# d701-vs1053-synth.net
KiCad netlist of a schematic drawn in EAGLE
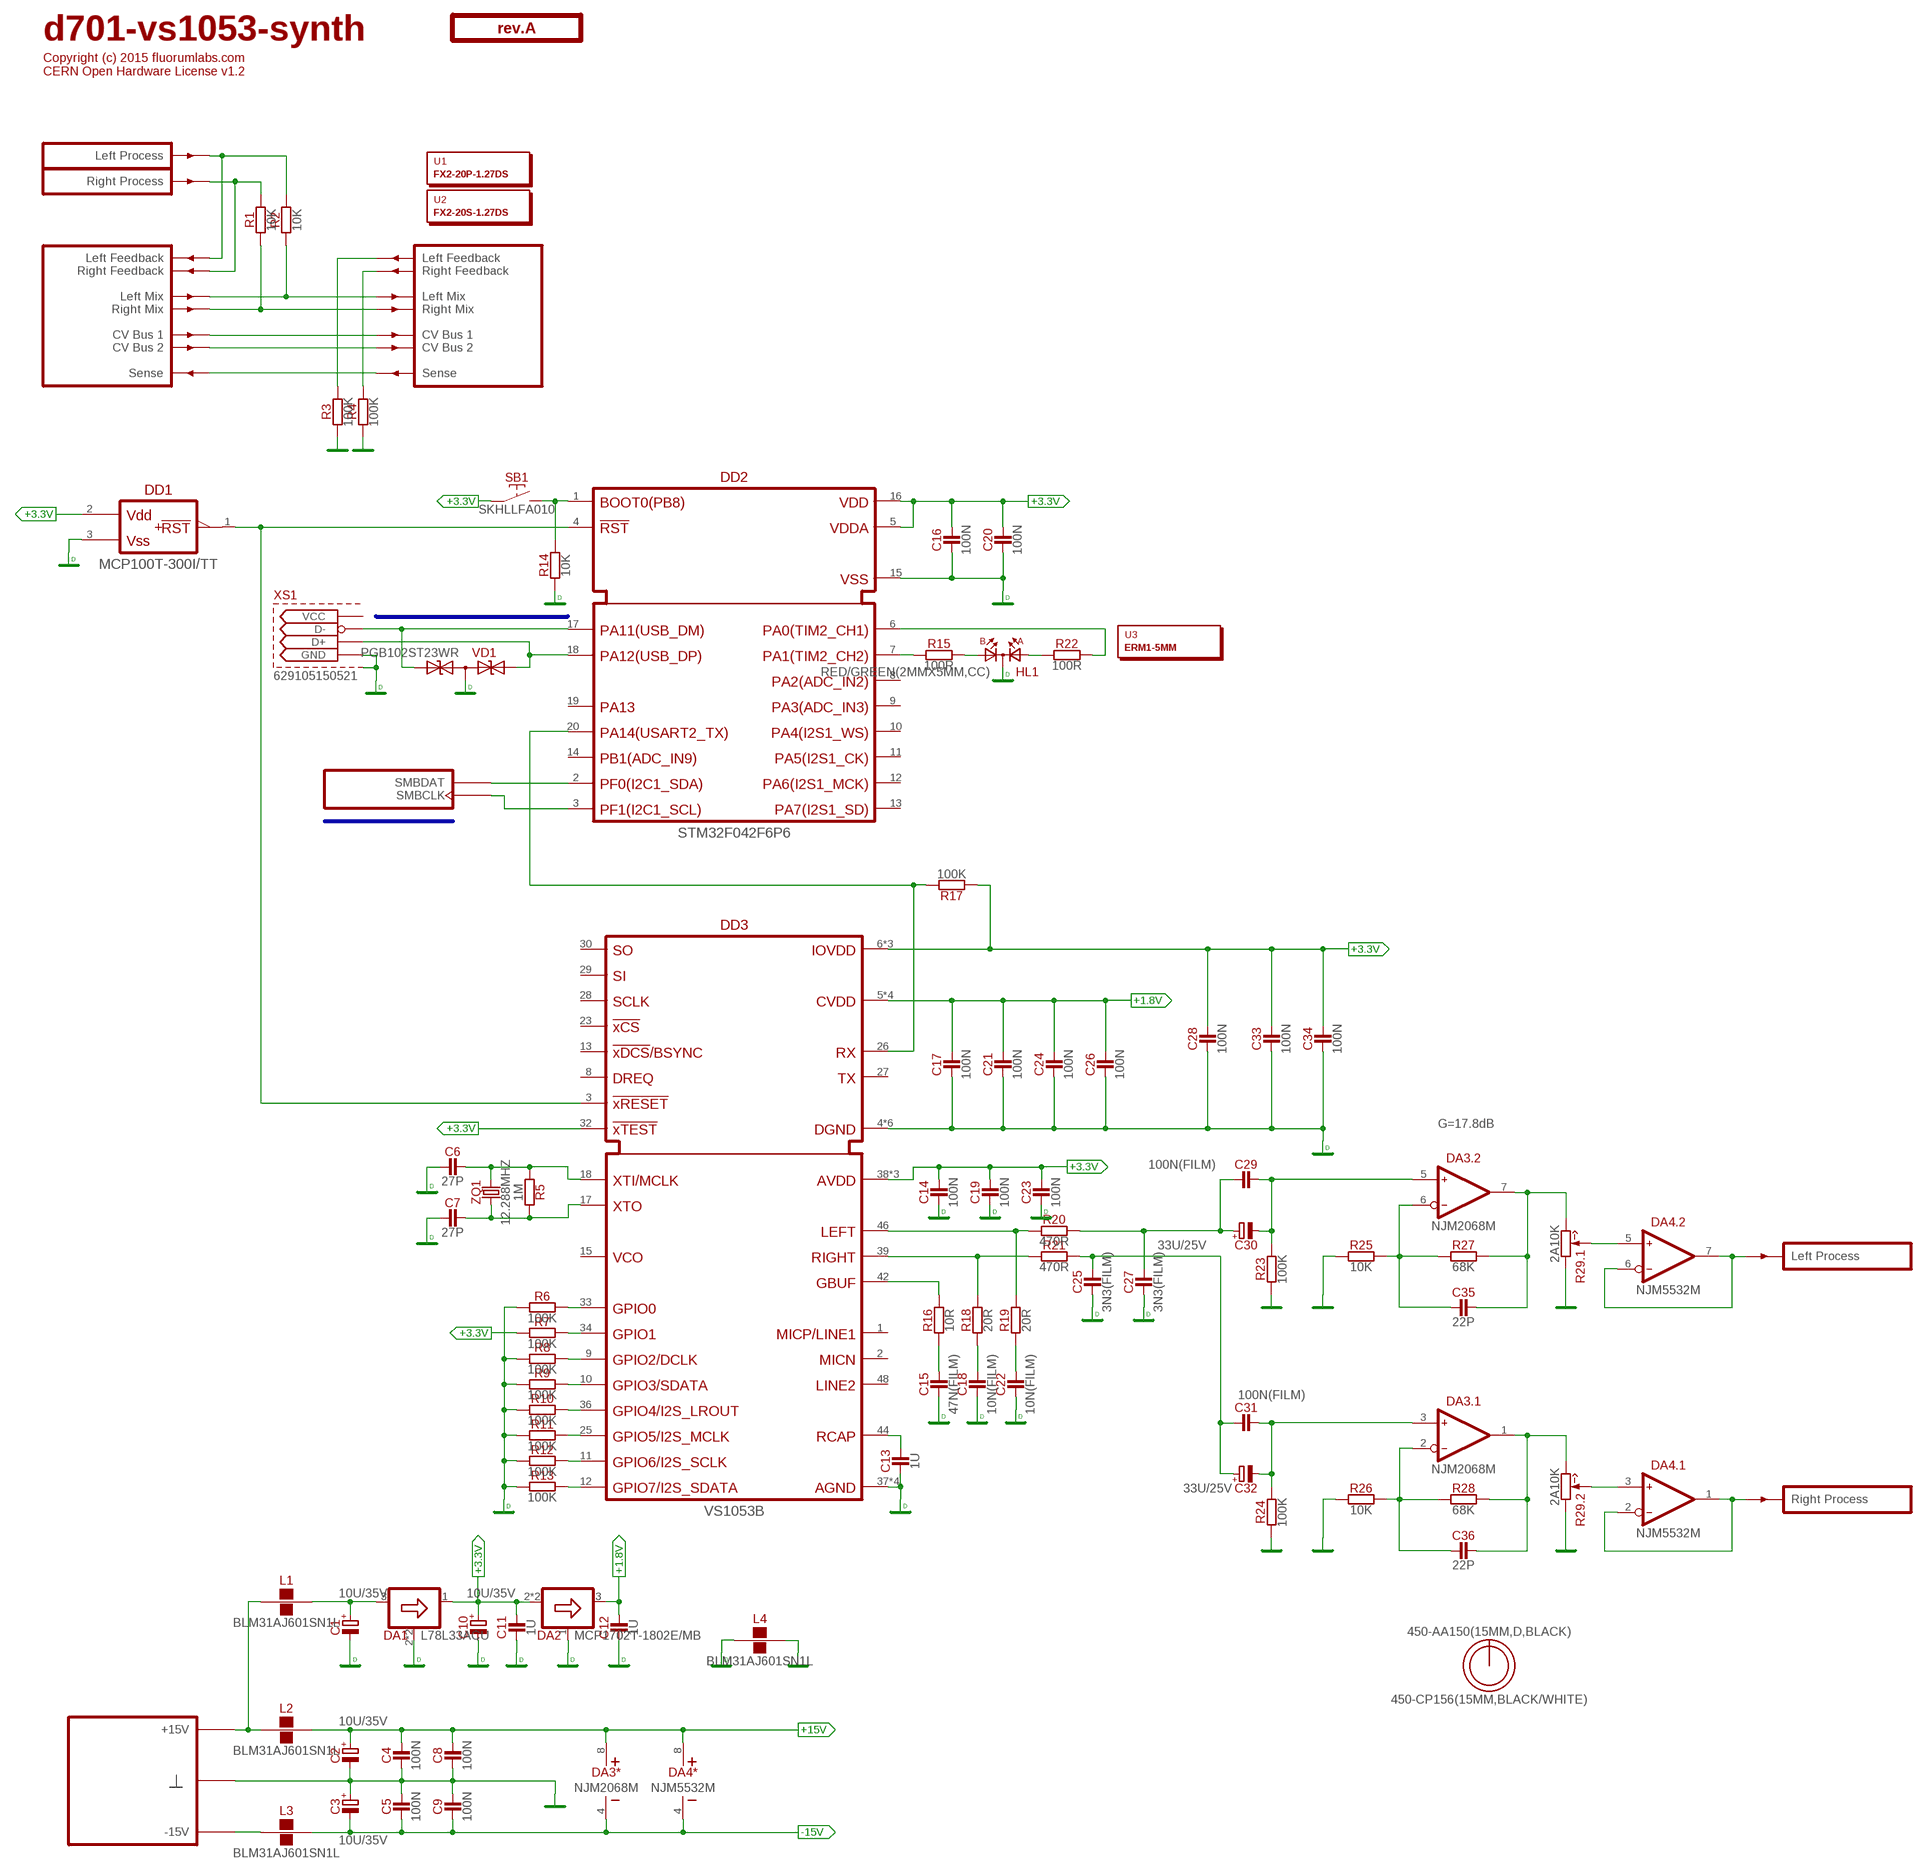
[diagram p0: schematic, sheet 1]

(export (version "E")
  (design (tool "Eeschema 10.0.6"))
  (components
    (comp (ref "C1")
      (value "10U/35V")
      (footprint "eagle-import:E2-5")
      (libsource (lib "eagle-import") (part "?10U/35V"))
    )
    (comp (ref "C2")
      (value "10U/35V")
      (footprint "eagle-import:E2-5")
      (libsource (lib "eagle-import") (part "?10U/35V"))
    )
    (comp (ref "C3")
      (value "10U/35V")
      (footprint "eagle-import:E2-5")
      (libsource (lib "eagle-import") (part "?10U/35V"))
    )
    (comp (ref "C4")
      (value "100N")
      (footprint "eagle-import:C-0805")
      (libsource (lib "eagle-import") (part "?100N"))
    )
    (comp (ref "C5")
      (value "100N")
      (footprint "eagle-import:C-0805")
      (libsource (lib "eagle-import") (part "?100N"))
    )
    (comp (ref "C6")
      (value "27P")
      (footprint "eagle-import:C-0805")
      (libsource (lib "eagle-import") (part "?27P"))
    )
    (comp (ref "C7")
      (value "27P")
      (footprint "eagle-import:C-0805")
      (libsource (lib "eagle-import") (part "?27P"))
    )
    (comp (ref "C8")
      (value "100N")
      (footprint "eagle-import:C-0805")
      (libsource (lib "eagle-import") (part "?100N"))
    )
    (comp (ref "C9")
      (value "100N")
      (footprint "eagle-import:C-0805")
      (libsource (lib "eagle-import") (part "?100N"))
    )
    (comp (ref "C10")
      (value "10U/35V")
      (footprint "eagle-import:E2-5")
      (libsource (lib "eagle-import") (part "?10U/35V"))
    )
    (comp (ref "C11")
      (value "1U")
      (footprint "eagle-import:C-0805")
      (libsource (lib "eagle-import") (part "?1U"))
    )
    (comp (ref "C12")
      (value "1U")
      (footprint "eagle-import:C-0805")
      (libsource (lib "eagle-import") (part "?1U"))
    )
    (comp (ref "C13")
      (value "1U")
      (footprint "eagle-import:C-0805")
      (libsource (lib "eagle-import") (part "?1U"))
    )
    (comp (ref "C14")
      (value "100N")
      (footprint "eagle-import:C-0805")
      (libsource (lib "eagle-import") (part "?100N"))
    )
    (comp (ref "C15")
      (value "47N(FILM)")
      (footprint "eagle-import:C050-025X075")
      (libsource (lib "eagle-import") (part "?47N(FILM)"))
    )
    (comp (ref "C16")
      (value "100N")
      (footprint "eagle-import:C-0805")
      (libsource (lib "eagle-import") (part "?100N"))
    )
    (comp (ref "C17")
      (value "100N")
      (footprint "eagle-import:C-0805")
      (libsource (lib "eagle-import") (part "?100N"))
    )
    (comp (ref "C18")
      (value "10N(FILM)")
      (footprint "eagle-import:C050-025X075")
      (libsource (lib "eagle-import") (part "?10N(FILM)"))
    )
    (comp (ref "C19")
      (value "100N")
      (footprint "eagle-import:C-0805")
      (libsource (lib "eagle-import") (part "?100N"))
    )
    (comp (ref "C20")
      (value "100N")
      (footprint "eagle-import:C-0805")
      (libsource (lib "eagle-import") (part "?100N"))
    )
    (comp (ref "C21")
      (value "100N")
      (footprint "eagle-import:C-0805")
      (libsource (lib "eagle-import") (part "?100N"))
    )
    (comp (ref "C22")
      (value "10N(FILM)")
      (footprint "eagle-import:C050-025X075")
      (libsource (lib "eagle-import") (part "?10N(FILM)"))
    )
    (comp (ref "C23")
      (value "100N")
      (footprint "eagle-import:C-0805")
      (libsource (lib "eagle-import") (part "?100N"))
    )
    (comp (ref "C24")
      (value "100N")
      (footprint "eagle-import:C-0805")
      (libsource (lib "eagle-import") (part "?100N"))
    )
    (comp (ref "C25")
      (value "3N3(FILM)")
      (footprint "eagle-import:C050-025X075")
      (libsource (lib "eagle-import") (part "?3N3(FILM)"))
    )
    (comp (ref "C26")
      (value "100N")
      (footprint "eagle-import:C-0805")
      (libsource (lib "eagle-import") (part "?100N"))
    )
    (comp (ref "C27")
      (value "3N3(FILM)")
      (footprint "eagle-import:C050-025X075")
      (libsource (lib "eagle-import") (part "?3N3(FILM)"))
    )
    (comp (ref "C28")
      (value "100N")
      (footprint "eagle-import:C-0805")
      (libsource (lib "eagle-import") (part "?100N"))
    )
    (comp (ref "C29")
      (value "100N(FILM)")
      (footprint "eagle-import:C050-025X075")
      (libsource (lib "eagle-import") (part "?100N(FILM)"))
    )
    (comp (ref "C30")
      (value "33U/25V")
      (footprint "eagle-import:E2,5-7")
      (libsource (lib "eagle-import") (part "?33U/25V"))
    )
    (comp (ref "C31")
      (value "100N(FILM)")
      (footprint "eagle-import:C050-025X075")
      (libsource (lib "eagle-import") (part "?100N(FILM)"))
    )
    (comp (ref "C32")
      (value "33U/25V")
      (footprint "eagle-import:E2,5-7")
      (libsource (lib "eagle-import") (part "?33U/25V"))
    )
    (comp (ref "C33")
      (value "100N")
      (footprint "eagle-import:C-0805")
      (libsource (lib "eagle-import") (part "?100N"))
    )
    (comp (ref "C34")
      (value "100N")
      (footprint "eagle-import:C-0805")
      (libsource (lib "eagle-import") (part "?100N"))
    )
    (comp (ref "C35")
      (value "22P")
      (footprint "eagle-import:C-0805")
      (libsource (lib "eagle-import") (part "?22P"))
    )
    (comp (ref "C36")
      (value "22P")
      (footprint "eagle-import:C-0805")
      (libsource (lib "eagle-import") (part "?22P"))
    )
    (comp (ref "DA1")
      (value "L78L33ACU")
      (footprint "eagle-import:SOT89")
      (libsource (lib "eagle-import") (part "?L78L33ACU"))
    )
    (comp (ref "DA2")
      (value "MCP1702T-1802E/MB")
      (footprint "eagle-import:SOT89")
      (libsource (lib "eagle-import") (part "?MCP1702T-1802E/MB"))
    )
    (comp (ref "DA3")
      (value "NJM2068M")
      (footprint "eagle-import:SO-8")
      (libsource (lib "eagle-import") (part "NJM2068M"))
    )
    (comp (ref "DA4")
      (value "NJM5532M")
      (footprint "eagle-import:SO-8")
      (libsource (lib "eagle-import") (part "NJM5532M"))
    )
    (comp (ref "DD1")
      (value "MCP100T-300I/TT")
      (footprint "eagle-import:SOT23")
      (libsource (lib "eagle-import") (part "MCP100T-300I/TT"))
    )
    (comp (ref "DD2")
      (value "STM32F042F6P6")
      (footprint "eagle-import:TSSOP20")
      (libsource (lib "eagle-import") (part "STM32F042F6P6"))
    )
    (comp (ref "DD3")
      (value "VS1053B")
      (footprint "eagle-import:LQFP48-7X7")
      (libsource (lib "eagle-import") (part "VS1053B"))
    )
    (comp (ref "HL1")
      (value "RED/GREEN(2MMX5MM,CC)")
      (footprint "eagle-import:LED2X5-3PIN")
      (libsource (lib "eagle-import") (part "?(2MMX5MM,CC)RED/GREEN"))
    )
    (comp (ref "L1")
      (value "BLM31AJ601SN1L")
      (footprint "eagle-import:1206")
      (libsource (lib "eagle-import") (part "BLM31AJ601SN1L"))
    )
    (comp (ref "L2")
      (value "BLM31AJ601SN1L")
      (footprint "eagle-import:1206")
      (libsource (lib "eagle-import") (part "BLM31AJ601SN1L"))
    )
    (comp (ref "L3")
      (value "BLM31AJ601SN1L")
      (footprint "eagle-import:1206")
      (libsource (lib "eagle-import") (part "BLM31AJ601SN1L"))
    )
    (comp (ref "L4")
      (value "BLM31AJ601SN1L")
      (footprint "eagle-import:1206")
      (libsource (lib "eagle-import") (part "BLM31AJ601SN1L"))
    )
    (comp (ref "O1")
      (value "TITLE")
      (footprint "eagle-import:EMPTY")
      (libsource (lib "eagle-import") (part "TITLE"))
    )
    (comp (ref "O2")
      (value "450-AA150(15MM,D,BLACK)")
      (footprint "eagle-import:EMPTY")
      (libsource (lib "eagle-import") (part "450-AA?150(15MM,D,BLACK)"))
    )
    (comp (ref "O3")
      (value "450-CP156(15MM,BLACK/WHITE)")
      (footprint "eagle-import:EMPTY")
      (libsource (lib "eagle-import") (part "450-C?P156(15MM,BLACK/WHITE)"))
    )
    (comp (ref "PCB1")
      (value "rev.A")
      (footprint "eagle-import:ST2-BOARD-50")
      (libsource (lib "eagle-import") (part "ST2-BOARD-?50"))
    )
    (comp (ref "R1")
      (value "10K")
      (footprint "eagle-import:R-0805")
      (libsource (lib "eagle-import") (part "?10K"))
    )
    (comp (ref "R2")
      (value "10K")
      (footprint "eagle-import:R-0805")
      (libsource (lib "eagle-import") (part "?10K"))
    )
    (comp (ref "R3")
      (value "100K")
      (footprint "eagle-import:R-0805")
      (libsource (lib "eagle-import") (part "?100K"))
    )
    (comp (ref "R4")
      (value "100K")
      (footprint "eagle-import:R-0805")
      (libsource (lib "eagle-import") (part "?100K"))
    )
    (comp (ref "R5")
      (value "1M")
      (footprint "eagle-import:R-0805")
      (libsource (lib "eagle-import") (part "?1M"))
    )
    (comp (ref "R6")
      (value "100K")
      (footprint "eagle-import:R-0805")
      (libsource (lib "eagle-import") (part "?100K"))
    )
    (comp (ref "R7")
      (value "100K")
      (footprint "eagle-import:R-0805")
      (libsource (lib "eagle-import") (part "?100K"))
    )
    (comp (ref "R8")
      (value "100K")
      (footprint "eagle-import:R-0805")
      (libsource (lib "eagle-import") (part "?100K"))
    )
    (comp (ref "R9")
      (value "100K")
      (footprint "eagle-import:R-0805")
      (libsource (lib "eagle-import") (part "?100K"))
    )
    (comp (ref "R10")
      (value "100K")
      (footprint "eagle-import:R-0805")
      (libsource (lib "eagle-import") (part "?100K"))
    )
    (comp (ref "R11")
      (value "100K")
      (footprint "eagle-import:R-0805")
      (libsource (lib "eagle-import") (part "?100K"))
    )
    (comp (ref "R12")
      (value "100K")
      (footprint "eagle-import:R-0805")
      (libsource (lib "eagle-import") (part "?100K"))
    )
    (comp (ref "R13")
      (value "100K")
      (footprint "eagle-import:R-0805")
      (libsource (lib "eagle-import") (part "?100K"))
    )
    (comp (ref "R14")
      (value "10K")
      (footprint "eagle-import:R-0805")
      (libsource (lib "eagle-import") (part "?10K"))
    )
    (comp (ref "R15")
      (value "100R")
      (footprint "eagle-import:R-0805")
      (libsource (lib "eagle-import") (part "?100R"))
    )
    (comp (ref "R16")
      (value "10R")
      (footprint "eagle-import:R-0805")
      (libsource (lib "eagle-import") (part "?10R"))
    )
    (comp (ref "R17")
      (value "100K")
      (footprint "eagle-import:R-0805")
      (libsource (lib "eagle-import") (part "?100K"))
    )
    (comp (ref "R18")
      (value "20R")
      (footprint "eagle-import:R-0805")
      (libsource (lib "eagle-import") (part "?20R"))
    )
    (comp (ref "R19")
      (value "20R")
      (footprint "eagle-import:R-0805")
      (libsource (lib "eagle-import") (part "?20R"))
    )
    (comp (ref "R20")
      (value "470R")
      (footprint "eagle-import:R-0805")
      (libsource (lib "eagle-import") (part "?470R"))
    )
    (comp (ref "R21")
      (value "470R")
      (footprint "eagle-import:R-0805")
      (libsource (lib "eagle-import") (part "?470R"))
    )
    (comp (ref "R22")
      (value "100R")
      (footprint "eagle-import:R-0805")
      (libsource (lib "eagle-import") (part "?100R"))
    )
    (comp (ref "R23")
      (value "100K")
      (footprint "eagle-import:R-0805")
      (libsource (lib "eagle-import") (part "?100K"))
    )
    (comp (ref "R24")
      (value "100K")
      (footprint "eagle-import:R-0805")
      (libsource (lib "eagle-import") (part "?100K"))
    )
    (comp (ref "R25")
      (value "10K")
      (footprint "eagle-import:R-0805")
      (libsource (lib "eagle-import") (part "?10K"))
    )
    (comp (ref "R26")
      (value "10K")
      (footprint "eagle-import:R-0805")
      (libsource (lib "eagle-import") (part "?10K"))
    )
    (comp (ref "R27")
      (value "68K")
      (footprint "eagle-import:R-0805")
      (libsource (lib "eagle-import") (part "?68K"))
    )
    (comp (ref "R28")
      (value "68K")
      (footprint "eagle-import:R-0805")
      (libsource (lib "eagle-import") (part "?68K"))
    )
    (comp (ref "R29")
      (value "2A10K")
      (footprint "eagle-import:RV11-DUAL")
      (libsource (lib "eagle-import") (part "2?A10K"))
    )
    (comp (ref "SB1")
      (value "SKHLLFA010")
      (footprint "eagle-import:SKHLLFA010")
      (libsource (lib "eagle-import") (part "SKHLLFA010"))
    )
    (comp (ref "U1")
      (value "FX2-20P-1.27DS")
      (footprint "eagle-import:EMPTY")
      (libsource (lib "eagle-import") (part "?FX2-20P-1.27DS"))
    )
    (comp (ref "U2")
      (value "FX2-20S-1.27DS")
      (footprint "eagle-import:EMPTY")
      (libsource (lib "eagle-import") (part "?FX2-20S-1.27DS"))
    )
    (comp (ref "U3")
      (value "ERM1-5MM")
      (footprint "eagle-import:EMPTY")
      (libsource (lib "eagle-import") (part "?ERM1-5MM"))
    )
    (comp (ref "VD1")
      (value "PGB102ST23WR")
      (footprint "eagle-import:SOT23")
      (libsource (lib "eagle-import") (part "PGB102ST23WR"))
    )
    (comp (ref "XS1")
      (value "629105150521")
      (footprint "eagle-import:MICROUSB-WURTH")
      (libsource (lib "eagle-import") (part "629105150521"))
    )
    (comp (ref "ZQ1")
      (value "12.288MHZ")
      (footprint "eagle-import:3225")
      (libsource (lib "eagle-import") (part "?12.288MHZ"))
    )
  )
  (nets
    (net (code "1") (name "+1.8V") (class "Default")
      (node (ref "C12") (pin "2") (pinfunction "2_2") (pintype "passive"))
      (node (ref "C17") (pin "2") (pinfunction "2_2") (pintype "passive"))
      (node (ref "C21") (pin "2") (pinfunction "2_2") (pintype "passive"))
      (node (ref "C24") (pin "2") (pinfunction "2_2") (pintype "passive"))
      (node (ref "C26") (pin "2") (pinfunction "2_2") (pintype "passive"))
      (node (ref "DA2") (pin "3") (pinfunction "OUT_3") (pintype "power_in"))
      (node (ref "DD3") (pin "24") (pinfunction "CVDD_24") (pintype "input"))
      (node (ref "DD3") (pin "31") (pinfunction "CVDD_31") (pintype "input"))
      (node (ref "DD3") (pin "5") (pinfunction "CVDD_5") (pintype "input"))
      (node (ref "DD3") (pin "7") (pinfunction "CVDD_7") (pintype "input"))
    )
    (net (code "2") (name "+3.3V") (class "Default")
      (node (ref "C10") (pin "+") (pinfunction "+_+") (pintype "passive"))
      (node (ref "C11") (pin "2") (pinfunction "2_2") (pintype "passive"))
      (node (ref "C14") (pin "2") (pinfunction "2_2") (pintype "passive"))
      (node (ref "C16") (pin "2") (pinfunction "2_2") (pintype "passive"))
      (node (ref "C19") (pin "2") (pinfunction "2_2") (pintype "passive"))
      (node (ref "C20") (pin "2") (pinfunction "2_2") (pintype "passive"))
      (node (ref "C23") (pin "2") (pinfunction "2_2") (pintype "passive"))
      (node (ref "C28") (pin "2") (pinfunction "2_2") (pintype "passive"))
      (node (ref "C33") (pin "2") (pinfunction "2_2") (pintype "passive"))
      (node (ref "C34") (pin "2") (pinfunction "2_2") (pintype "passive"))
      (node (ref "DA1") (pin "1") (pinfunction "OUT_1") (pintype "power_in"))
      (node (ref "DA2") (pin "2") (pinfunction "IN_2") (pintype "power_in"))
      (node (ref "DA2") (pin "2@1") (pinfunction "IN_2@1") (pintype "power_in"))
      (node (ref "DD1") (pin "2") (pinfunction "VDD_2") (pintype "input"))
      (node (ref "DD2") (pin "16") (pinfunction "VDD_16") (pintype "input"))
      (node (ref "DD2") (pin "5") (pinfunction "VDDA_5") (pintype "input"))
      (node (ref "DD3") (pin "14") (pinfunction "IOVDD_14") (pintype "input"))
      (node (ref "DD3") (pin "19") (pinfunction "IOVDD_19") (pintype "input"))
      (node (ref "DD3") (pin "32") (pinfunction "~{XTEST}_32") (pintype "input"))
      (node (ref "DD3") (pin "38") (pinfunction "AVDD_38") (pintype "input"))
      (node (ref "DD3") (pin "43") (pinfunction "AVDD_43") (pintype "input"))
      (node (ref "DD3") (pin "45") (pinfunction "AVDD_45") (pintype "input"))
      (node (ref "DD3") (pin "6") (pinfunction "IOVDD_6") (pintype "input"))
      (node (ref "R17") (pin "1") (pinfunction "1_1") (pintype "passive"))
      (node (ref "R7") (pin "1") (pinfunction "1_1") (pintype "passive"))
      (node (ref "SB1") (pin "1") (pinfunction "1_1") (pintype "passive"))
    )
    (net (code "3") (name "+15V") (class "Default")
      (node (ref "C2") (pin "+") (pinfunction "+_+") (pintype "passive"))
      (node (ref "C4") (pin "2") (pinfunction "2_2") (pintype "passive"))
      (node (ref "C8") (pin "2") (pinfunction "2_2") (pintype "passive"))
      (node (ref "DA3") (pin "8") (pinfunction "V+_8") (pintype "power_in"))
      (node (ref "DA4") (pin "8") (pinfunction "V+_8") (pintype "power_in"))
      (node (ref "L2") (pin "2") (pinfunction "2_2") (pintype "passive"))
    )
    (net (code "4") (name "-15V") (class "Default")
      (node (ref "C3") (pin "-") (pinfunction "-_-") (pintype "passive"))
      (node (ref "C5") (pin "1") (pinfunction "1_1") (pintype "passive"))
      (node (ref "C9") (pin "1") (pinfunction "1_1") (pintype "passive"))
      (node (ref "DA3") (pin "4") (pinfunction "V-_4") (pintype "power_in"))
      (node (ref "DA4") (pin "4") (pinfunction "V-_4") (pintype "power_in"))
      (node (ref "L3") (pin "2") (pinfunction "2_2") (pintype "passive"))
    )
    (net (code "5") (name "DGND") (class "Default")
      (node (ref "C1") (pin "-") (pinfunction "-_-") (pintype "passive"))
      (node (ref "C10") (pin "-") (pinfunction "-_-") (pintype "passive"))
      (node (ref "C11") (pin "1") (pinfunction "1_1") (pintype "passive"))
      (node (ref "C12") (pin "1") (pinfunction "1_1") (pintype "passive"))
      (node (ref "C13") (pin "1") (pinfunction "1_1") (pintype "passive"))
      (node (ref "C14") (pin "1") (pinfunction "1_1") (pintype "passive"))
      (node (ref "C15") (pin "1") (pinfunction "1_1") (pintype "passive"))
      (node (ref "C16") (pin "1") (pinfunction "1_1") (pintype "passive"))
      (node (ref "C17") (pin "1") (pinfunction "1_1") (pintype "passive"))
      (node (ref "C18") (pin "1") (pinfunction "1_1") (pintype "passive"))
      (node (ref "C19") (pin "1") (pinfunction "1_1") (pintype "passive"))
      (node (ref "C20") (pin "1") (pinfunction "1_1") (pintype "passive"))
      (node (ref "C21") (pin "1") (pinfunction "1_1") (pintype "passive"))
      (node (ref "C22") (pin "1") (pinfunction "1_1") (pintype "passive"))
      (node (ref "C23") (pin "1") (pinfunction "1_1") (pintype "passive"))
      (node (ref "C24") (pin "1") (pinfunction "1_1") (pintype "passive"))
      (node (ref "C25") (pin "1") (pinfunction "1_1") (pintype "passive"))
      (node (ref "C26") (pin "1") (pinfunction "1_1") (pintype "passive"))
      (node (ref "C27") (pin "1") (pinfunction "1_1") (pintype "passive"))
      (node (ref "C28") (pin "1") (pinfunction "1_1") (pintype "passive"))
      (node (ref "C33") (pin "1") (pinfunction "1_1") (pintype "passive"))
      (node (ref "C34") (pin "1") (pinfunction "1_1") (pintype "passive"))
      (node (ref "C6") (pin "1") (pinfunction "1_1") (pintype "passive"))
      (node (ref "C7") (pin "1") (pinfunction "1_1") (pintype "passive"))
      (node (ref "DA1") (pin "2") (pinfunction "GND_2") (pintype "power_in"))
      (node (ref "DA1") (pin "2@1") (pinfunction "GND_2@1") (pintype "power_in"))
      (node (ref "DA2") (pin "1") (pinfunction "GND_1") (pintype "power_in"))
      (node (ref "DD1") (pin "3") (pinfunction "VSS_3") (pintype "passive"))
      (node (ref "DD2") (pin "15") (pinfunction "VSS_15") (pintype "input"))
      (node (ref "DD3") (pin "16") (pinfunction "DGND_16") (pintype "input"))
      (node (ref "DD3") (pin "20") (pinfunction "DGND_20") (pintype "input"))
      (node (ref "DD3") (pin "21") (pinfunction "DGND_21") (pintype "input"))
      (node (ref "DD3") (pin "22") (pinfunction "DGND_22") (pintype "input"))
      (node (ref "DD3") (pin "35") (pinfunction "DGND_35") (pintype "input"))
      (node (ref "DD3") (pin "37") (pinfunction "AGND_37") (pintype "input"))
      (node (ref "DD3") (pin "4") (pinfunction "DGND_4") (pintype "input"))
      (node (ref "DD3") (pin "40") (pinfunction "AGND_40") (pintype "input"))
      (node (ref "DD3") (pin "41") (pinfunction "AGND_41") (pintype "input"))
      (node (ref "DD3") (pin "47") (pinfunction "AGND_47") (pintype "input"))
      (node (ref "HL1") (pin "K") (pinfunction "K_K") (pintype "passive"))
      (node (ref "L4") (pin "1") (pinfunction "1_1") (pintype "passive"))
      (node (ref "R10") (pin "1") (pinfunction "1_1") (pintype "passive"))
      (node (ref "R11") (pin "1") (pinfunction "1_1") (pintype "passive"))
      (node (ref "R12") (pin "1") (pinfunction "1_1") (pintype "passive"))
      (node (ref "R13") (pin "1") (pinfunction "1_1") (pintype "passive"))
      (node (ref "R14") (pin "1") (pinfunction "1_1") (pintype "passive"))
      (node (ref "R6") (pin "1") (pinfunction "1_1") (pintype "passive"))
      (node (ref "R8") (pin "1") (pinfunction "1_1") (pintype "passive"))
      (node (ref "R9") (pin "1") (pinfunction "1_1") (pintype "passive"))
      (node (ref "VD1") (pin "3") (pinfunction "C_3") (pintype "passive"))
      (node (ref "XS1") (pin "5") (pinfunction "GND_5") (pintype "passive"))
      (node (ref "XS1") (pin "S1") (pinfunction "S1_S1") (pintype "passive"))
      (node (ref "XS1") (pin "S2") (pinfunction "S1_S2") (pintype "passive"))
      (node (ref "XS1") (pin "S3") (pinfunction "S1_S3") (pintype "passive"))
      (node (ref "XS1") (pin "S4") (pinfunction "S1_S4") (pintype "passive"))
      (node (ref "XS1") (pin "S5") (pinfunction "S1_S5") (pintype "passive"))
      (node (ref "XS1") (pin "S6") (pinfunction "S1_S6") (pintype "passive"))
    )
    (net (code "6") (name "GND") (class "Default")
      (node (ref "C2") (pin "-") (pinfunction "-_-") (pintype "passive"))
      (node (ref "C3") (pin "+") (pinfunction "+_+") (pintype "passive"))
      (node (ref "C4") (pin "1") (pinfunction "1_1") (pintype "passive"))
      (node (ref "C5") (pin "2") (pinfunction "2_2") (pintype "passive"))
      (node (ref "C8") (pin "1") (pinfunction "1_1") (pintype "passive"))
      (node (ref "C9") (pin "2") (pinfunction "2_2") (pintype "passive"))
      (node (ref "L4") (pin "2") (pinfunction "2_2") (pintype "passive"))
      (node (ref "PCB1") (pin "B4") (pinfunction "GND_B4") (pintype "bidirectional"))
      (node (ref "PCB1") (pin "B4'") (pinfunction "GND_B4'") (pintype "bidirectional"))
      (node (ref "PCB1") (pin "B5") (pinfunction "GND_B5") (pintype "bidirectional"))
      (node (ref "PCB1") (pin "B5'") (pinfunction "GND_B5'") (pintype "bidirectional"))
      (node (ref "PCB1") (pin "B6") (pinfunction "GND_B6") (pintype "bidirectional"))
      (node (ref "PCB1") (pin "B6'") (pinfunction "GND_B6'") (pintype "bidirectional"))
      (node (ref "PCB1") (pin "B7") (pinfunction "GND_B7") (pintype "bidirectional"))
      (node (ref "PCB1") (pin "B7'") (pinfunction "GND_B7'") (pintype "bidirectional"))
      (node (ref "PCB1") (pin "B8") (pinfunction "GND_B8") (pintype "bidirectional"))
      (node (ref "PCB1") (pin "B8'") (pinfunction "GND_B8'") (pintype "bidirectional"))
      (node (ref "R23") (pin "1") (pinfunction "1_1") (pintype "passive"))
      (node (ref "R24") (pin "1") (pinfunction "1_1") (pintype "passive"))
      (node (ref "R25") (pin "1") (pinfunction "1_1") (pintype "passive"))
      (node (ref "R26") (pin "1") (pinfunction "1_1") (pintype "passive"))
      (node (ref "R29") (pin "1") (pinfunction "CCW_1") (pintype "passive"))
      (node (ref "R29") (pin "1'") (pinfunction "CCW_1'") (pintype "passive"))
      (node (ref "R3") (pin "1") (pinfunction "1_1") (pintype "passive"))
      (node (ref "R4") (pin "1") (pinfunction "1_1") (pintype "passive"))
    )
    (net (code "7") (name "Net-(C15-Pad2)") (class "Default")
      (node (ref "C15") (pin "2") (pinfunction "2_2") (pintype "passive"))
      (node (ref "R16") (pin "1") (pinfunction "1_1") (pintype "passive"))
    )
    (net (code "8") (name "Net-(C18-Pad2)") (class "Default")
      (node (ref "C18") (pin "2") (pinfunction "2_2") (pintype "passive"))
      (node (ref "R18") (pin "1") (pinfunction "1_1") (pintype "passive"))
    )
    (net (code "9") (name "Net-(C22-Pad2)") (class "Default")
      (node (ref "C22") (pin "2") (pinfunction "2_2") (pintype "passive"))
      (node (ref "R19") (pin "1") (pinfunction "1_1") (pintype "passive"))
    )
    (net (code "10") (name "Net-(C25-Pad2)") (class "Default")
      (node (ref "C25") (pin "2") (pinfunction "2_2") (pintype "passive"))
      (node (ref "C31") (pin "1") (pinfunction "1_1") (pintype "passive"))
      (node (ref "C32") (pin "+") (pinfunction "+_+") (pintype "passive"))
      (node (ref "R21") (pin "2") (pinfunction "2_2") (pintype "passive"))
    )
    (net (code "11") (name "Net-(C27-Pad2)") (class "Default")
      (node (ref "C27") (pin "2") (pinfunction "2_2") (pintype "passive"))
      (node (ref "C29") (pin "1") (pinfunction "1_1") (pintype "passive"))
      (node (ref "C30") (pin "+") (pinfunction "+_+") (pintype "passive"))
      (node (ref "R20") (pin "2") (pinfunction "2_2") (pintype "passive"))
    )
    (net (code "12") (name "Net-(DA1-IN)") (class "Default")
      (node (ref "C1") (pin "+") (pinfunction "+_+") (pintype "passive"))
      (node (ref "DA1") (pin "3") (pinfunction "IN_3") (pintype "power_in"))
      (node (ref "L1") (pin "2") (pinfunction "2_2") (pintype "passive"))
    )
    (net (code "13") (name "Net-(DA3B-IN+)") (class "Default")
      (node (ref "C31") (pin "2") (pinfunction "2_2") (pintype "passive"))
      (node (ref "C32") (pin "-") (pinfunction "-_-") (pintype "passive"))
      (node (ref "DA3") (pin "3") (pinfunction "IN+_3") (pintype "input"))
      (node (ref "R24") (pin "2") (pinfunction "2_2") (pintype "passive"))
    )
    (net (code "14") (name "Net-(DA3B-IN-)") (class "Default")
      (node (ref "C36") (pin "1") (pinfunction "1_1") (pintype "passive"))
      (node (ref "DA3") (pin "2") (pinfunction "IN-_2") (pintype "input"))
      (node (ref "R26") (pin "2") (pinfunction "2_2") (pintype "passive"))
      (node (ref "R28") (pin "1") (pinfunction "1_1") (pintype "passive"))
    )
    (net (code "15") (name "Net-(DA3B-OUT)") (class "Default")
      (node (ref "C36") (pin "2") (pinfunction "2_2") (pintype "passive"))
      (node (ref "DA3") (pin "1") (pinfunction "OUT_1") (pintype "output"))
      (node (ref "R28") (pin "2") (pinfunction "2_2") (pintype "passive"))
      (node (ref "R29") (pin "3'") (pinfunction "CW_3'") (pintype "passive"))
    )
    (net (code "16") (name "Net-(DA3C-IN+)") (class "Default")
      (node (ref "C29") (pin "2") (pinfunction "2_2") (pintype "passive"))
      (node (ref "C30") (pin "-") (pinfunction "-_-") (pintype "passive"))
      (node (ref "DA3") (pin "5") (pinfunction "IN+_5") (pintype "input"))
      (node (ref "R23") (pin "2") (pinfunction "2_2") (pintype "passive"))
    )
    (net (code "17") (name "Net-(DA3C-IN-)") (class "Default")
      (node (ref "C35") (pin "1") (pinfunction "1_1") (pintype "passive"))
      (node (ref "DA3") (pin "6") (pinfunction "IN-_6") (pintype "input"))
      (node (ref "R25") (pin "2") (pinfunction "2_2") (pintype "passive"))
      (node (ref "R27") (pin "1") (pinfunction "1_1") (pintype "passive"))
    )
    (net (code "18") (name "Net-(DA3C-OUT)") (class "Default")
      (node (ref "C35") (pin "2") (pinfunction "2_2") (pintype "passive"))
      (node (ref "DA3") (pin "7") (pinfunction "OUT_7") (pintype "output"))
      (node (ref "R27") (pin "2") (pinfunction "2_2") (pintype "passive"))
      (node (ref "R29") (pin "3") (pinfunction "CW_3") (pintype "passive"))
    )
    (net (code "19") (name "Net-(DA4B-IN+)") (class "Default")
      (node (ref "DA4") (pin "3") (pinfunction "IN+_3") (pintype "input"))
      (node (ref "R29") (pin "2'") (pinfunction "W_2'") (pintype "passive"))
    )
    (net (code "20") (name "Net-(DA4B-IN-)") (class "Default")
      (node (ref "DA4") (pin "1") (pinfunction "OUT_1") (pintype "output"))
      (node (ref "DA4") (pin "2") (pinfunction "IN-_2") (pintype "input"))
      (node (ref "PCB1") (pin "BOUTR'") (pinfunction "OUTR_BOUTR'") (pintype "bidirectional"))
    )
    (net (code "21") (name "Net-(DA4C-IN+)") (class "Default")
      (node (ref "DA4") (pin "5") (pinfunction "IN+_5") (pintype "input"))
      (node (ref "R29") (pin "2") (pinfunction "W_2") (pintype "passive"))
    )
    (net (code "22") (name "Net-(DA4C-IN-)") (class "Default")
      (node (ref "DA4") (pin "6") (pinfunction "IN-_6") (pintype "input"))
      (node (ref "DA4") (pin "7") (pinfunction "OUT_7") (pintype "output"))
      (node (ref "PCB1") (pin "BOUTL'") (pinfunction "OUTL_BOUTL'") (pintype "bidirectional"))
    )
    (net (code "23") (name "Net-(DD1-~{RST})") (class "Default")
      (node (ref "DD1") (pin "1") (pinfunction "~{RST}_1") (pintype "passive"))
      (node (ref "DD2") (pin "4") (pinfunction "~{RST}_4") (pintype "input"))
      (node (ref "DD3") (pin "3") (pinfunction "~{XRESET}_3") (pintype "input"))
    )
    (net (code "24") (name "Net-(DD2-BOOT0)") (class "Default")
      (node (ref "DD2") (pin "1") (pinfunction "BOOT0_1") (pintype "input"))
      (node (ref "R14") (pin "2") (pinfunction "2_2") (pintype "passive"))
      (node (ref "SB1") (pin "2") (pinfunction "2_2") (pintype "passive"))
    )
    (net (code "25") (name "Net-(DD2-PA0)") (class "Default")
      (node (ref "DD2") (pin "6") (pinfunction "PA0_6") (pintype "input"))
      (node (ref "R22") (pin "2") (pinfunction "2_2") (pintype "passive"))
    )
    (net (code "26") (name "Net-(DD2-PA1)") (class "Default")
      (node (ref "DD2") (pin "7") (pinfunction "PA1_7") (pintype "input"))
      (node (ref "R15") (pin "1") (pinfunction "1_1") (pintype "passive"))
    )
    (net (code "27") (name "Net-(DD2-PA11)") (class "Default")
      (node (ref "DD2") (pin "17") (pinfunction "PA11_17") (pintype "input"))
      (node (ref "VD1") (pin "2") (pinfunction "A1_2") (pintype "passive"))
      (node (ref "XS1") (pin "2") (pinfunction "D-_2") (pintype "bidirectional"))
    )
    (net (code "28") (name "Net-(DD2-PA12)") (class "Default")
      (node (ref "DD2") (pin "18") (pinfunction "PA12_18") (pintype "input"))
      (node (ref "VD1") (pin "1") (pinfunction "A_1") (pintype "passive"))
      (node (ref "XS1") (pin "3") (pinfunction "D+_3") (pintype "bidirectional"))
    )
    (net (code "29") (name "Net-(DD2-PA14)") (class "Default")
      (node (ref "DD2") (pin "20") (pinfunction "PA14_20") (pintype "input"))
      (node (ref "DD3") (pin "26") (pinfunction "RX_26") (pintype "input"))
      (node (ref "R17") (pin "2") (pinfunction "2_2") (pintype "passive"))
    )
    (net (code "30") (name "Net-(DD2-PF0)") (class "Default")
      (node (ref "DD2") (pin "2") (pinfunction "PF0_2") (pintype "input"))
      (node (ref "PCB1") (pin "ASMBDAT") (pinfunction "SMBDAT_ASMBDAT") (pintype "bidirectional"))
      (node (ref "PCB1") (pin "ASMBDAT'") (pinfunction "SMBDAT_ASMBDAT'") (pintype "bidirectional"))
    )
    (net (code "31") (name "Net-(DD2-PF1)") (class "Default")
      (node (ref "DD2") (pin "3") (pinfunction "PF1_3") (pintype "input"))
      (node (ref "PCB1") (pin "ASMBCLK") (pinfunction "SMBCLK_ASMBCLK") (pintype "bidirectional"))
      (node (ref "PCB1") (pin "ASMBCLK'") (pinfunction "SMBCLK_ASMBCLK'") (pintype "bidirectional"))
    )
    (net (code "32") (name "Net-(DD3-GBUF)") (class "Default")
      (node (ref "DD3") (pin "42") (pinfunction "GBUF_42") (pintype "input"))
      (node (ref "R16") (pin "2") (pinfunction "2_2") (pintype "passive"))
    )
    (net (code "33") (name "Net-(DD3-GPIO0)") (class "Default")
      (node (ref "DD3") (pin "33") (pinfunction "GPIO0_33") (pintype "input"))
      (node (ref "R6") (pin "2") (pinfunction "2_2") (pintype "passive"))
    )
    (net (code "34") (name "Net-(DD3-GPIO1)") (class "Default")
      (node (ref "DD3") (pin "34") (pinfunction "GPIO1_34") (pintype "input"))
      (node (ref "R7") (pin "2") (pinfunction "2_2") (pintype "passive"))
    )
    (net (code "35") (name "Net-(DD3-GPIO2{slash}DCLK)") (class "Default")
      (node (ref "DD3") (pin "9") (pinfunction "GPIO2/DCLK_9") (pintype "input"))
      (node (ref "R8") (pin "2") (pinfunction "2_2") (pintype "passive"))
    )
    (net (code "36") (name "Net-(DD3-GPIO3{slash}SDATA)") (class "Default")
      (node (ref "DD3") (pin "10") (pinfunction "GPIO3/SDATA_10") (pintype "input"))
      (node (ref "R9") (pin "2") (pinfunction "2_2") (pintype "passive"))
    )
    (net (code "37") (name "Net-(DD3-GPIO4{slash}I2S_LROUT)") (class "Default")
      (node (ref "DD3") (pin "36") (pinfunction "GPIO4/I2S_LROUT_36") (pintype "input"))
      (node (ref "R10") (pin "2") (pinfunction "2_2") (pintype "passive"))
    )
    (net (code "38") (name "Net-(DD3-GPIO5{slash}I2S_MCLK)") (class "Default")
      (node (ref "DD3") (pin "25") (pinfunction "GPIO5/I2S_MCLK_25") (pintype "input"))
      (node (ref "R11") (pin "2") (pinfunction "2_2") (pintype "passive"))
    )
    (net (code "39") (name "Net-(DD3-GPIO6{slash}I2S_SCLK)") (class "Default")
      (node (ref "DD3") (pin "11") (pinfunction "GPIO6/I2S_SCLK_11") (pintype "input"))
      (node (ref "R12") (pin "2") (pinfunction "2_2") (pintype "passive"))
    )
    (net (code "40") (name "Net-(DD3-GPIO7{slash}I2S_SDATA)") (class "Default")
      (node (ref "DD3") (pin "12") (pinfunction "GPIO7/I2S_SDATA_12") (pintype "input"))
      (node (ref "R13") (pin "2") (pinfunction "2_2") (pintype "passive"))
    )
    (net (code "41") (name "Net-(DD3-LEFT)") (class "Default")
      (node (ref "DD3") (pin "46") (pinfunction "LEFT_46") (pintype "input"))
      (node (ref "R19") (pin "2") (pinfunction "2_2") (pintype "passive"))
      (node (ref "R20") (pin "1") (pinfunction "1_1") (pintype "passive"))
    )
    (net (code "42") (name "Net-(DD3-RCAP)") (class "Default")
      (node (ref "C13") (pin "2") (pinfunction "2_2") (pintype "passive"))
      (node (ref "DD3") (pin "44") (pinfunction "RCAP_44") (pintype "input"))
    )
    (net (code "43") (name "Net-(DD3-RIGHT)") (class "Default")
      (node (ref "DD3") (pin "39") (pinfunction "RIGHT_39") (pintype "input"))
      (node (ref "R18") (pin "2") (pinfunction "2_2") (pintype "passive"))
      (node (ref "R21") (pin "1") (pinfunction "1_1") (pintype "passive"))
    )
    (net (code "44") (name "Net-(DD3-XTI{slash}MCLK)") (class "Default")
      (node (ref "C6") (pin "2") (pinfunction "2_2") (pintype "passive"))
      (node (ref "DD3") (pin "18") (pinfunction "XTI/MCLK_18") (pintype "input"))
      (node (ref "R5") (pin "1") (pinfunction "1_1") (pintype "passive"))
      (node (ref "ZQ1") (pin "3") (pinfunction "2_3") (pintype "passive"))
    )
    (net (code "45") (name "Net-(DD3-XTO)") (class "Default")
      (node (ref "C7") (pin "2") (pinfunction "2_2") (pintype "passive"))
      (node (ref "DD3") (pin "17") (pinfunction "XTO_17") (pintype "input"))
      (node (ref "R5") (pin "2") (pinfunction "2_2") (pintype "passive"))
      (node (ref "ZQ1") (pin "1") (pinfunction "1_1") (pintype "passive"))
    )
    (net (code "46") (name "Net-(HL1-PadA1)") (class "Default")
      (node (ref "HL1") (pin "A1") (pinfunction "A1_A1") (pintype "passive"))
      (node (ref "R22") (pin "1") (pinfunction "1_1") (pintype "passive"))
    )
    (net (code "47") (name "Net-(HL1-PadA2)") (class "Default")
      (node (ref "HL1") (pin "A2") (pinfunction "A2_A2") (pintype "passive"))
      (node (ref "R15") (pin "2") (pinfunction "2_2") (pintype "passive"))
    )
    (net (code "48") (name "Net-(L1-Pad1)") (class "Default")
      (node (ref "L1") (pin "1") (pinfunction "1_1") (pintype "passive"))
      (node (ref "L2") (pin "1") (pinfunction "1_1") (pintype "passive"))
      (node (ref "PCB1") (pin "A+15") (pinfunction "P+15V_A+15") (pintype "bidirectional"))
      (node (ref "PCB1") (pin "A+15'") (pinfunction "P+15V_A+15'") (pintype "bidirectional"))
      (node (ref "PCB1") (pin "B+15") (pinfunction "P+15V_B+15") (pintype "bidirectional"))
      (node (ref "PCB1") (pin "B+15'") (pinfunction "P+15V_B+15'") (pintype "bidirectional"))
    )
    (net (code "49") (name "Net-(L3-Pad1)") (class "Default")
      (node (ref "L3") (pin "1") (pinfunction "1_1") (pintype "passive"))
      (node (ref "PCB1") (pin "A-15") (pinfunction "P-15V_A-15") (pintype "bidirectional"))
      (node (ref "PCB1") (pin "A-15'") (pinfunction "P-15V_A-15'") (pintype "bidirectional"))
      (node (ref "PCB1") (pin "B-15") (pinfunction "P-15V_B-15") (pintype "bidirectional"))
      (node (ref "PCB1") (pin "B-15'") (pinfunction "P-15V_B-15'") (pintype "bidirectional"))
    )
    (net (code "50") (name "Net-(PCB1B-INL)") (class "Default")
      (node (ref "PCB1") (pin "ALFBK") (pinfunction "LFBK_ALFBK") (pintype "bidirectional"))
      (node (ref "PCB1") (pin "BINL") (pinfunction "INL_BINL") (pintype "bidirectional"))
      (node (ref "R2") (pin "2") (pinfunction "2_2") (pintype "passive"))
    )
    (net (code "51") (name "Net-(PCB1C-INR)") (class "Default")
      (node (ref "PCB1") (pin "ARFBK") (pinfunction "RFBK_ARFBK") (pintype "bidirectional"))
      (node (ref "PCB1") (pin "BINR") (pinfunction "INR_BINR") (pintype "bidirectional"))
      (node (ref "R1") (pin "2") (pinfunction "2_2") (pintype "passive"))
    )
    (net (code "52") (name "Net-(PCB1F-CV1)") (class "Default")
      (node (ref "PCB1") (pin "ACV1") (pinfunction "CV1_ACV1") (pintype "bidirectional"))
      (node (ref "PCB1") (pin "ACV1'") (pinfunction "CV1'_ACV1'") (pintype "bidirectional"))
    )
    (net (code "53") (name "Net-(PCB1F-CV2)") (class "Default")
      (node (ref "PCB1") (pin "ACV2") (pinfunction "CV2_ACV2") (pintype "bidirectional"))
      (node (ref "PCB1") (pin "ACV2'") (pinfunction "CV2'_ACV2'") (pintype "bidirectional"))
    )
    (net (code "54") (name "Net-(PCB1F-LMIX)") (class "Default")
      (node (ref "PCB1") (pin "ALMIX") (pinfunction "LMIX_ALMIX") (pintype "bidirectional"))
      (node (ref "PCB1") (pin "ALMIX'") (pinfunction "LMIX'_ALMIX'") (pintype "bidirectional"))
      (node (ref "R2") (pin "1") (pinfunction "1_1") (pintype "passive"))
    )
    (net (code "55") (name "Net-(PCB1F-RMIX)") (class "Default")
      (node (ref "PCB1") (pin "ARMIX") (pinfunction "RMIX_ARMIX") (pintype "bidirectional"))
      (node (ref "PCB1") (pin "ARMIX'") (pinfunction "RMIX'_ARMIX'") (pintype "bidirectional"))
      (node (ref "R1") (pin "1") (pinfunction "1_1") (pintype "passive"))
    )
    (net (code "56") (name "Net-(PCB1F-SENSE)") (class "Default")
      (node (ref "PCB1") (pin "BSENSE") (pinfunction "SENSE_BSENSE") (pintype "bidirectional"))
      (node (ref "PCB1") (pin "BSENSE'") (pinfunction "SENSE'_BSENSE'") (pintype "bidirectional"))
    )
    (net (code "57") (name "Net-(PCB1G-LFBK')") (class "Default")
      (node (ref "PCB1") (pin "ALFBK'") (pinfunction "LFBK'_ALFBK'") (pintype "bidirectional"))
      (node (ref "R3") (pin "2") (pinfunction "2_2") (pintype "passive"))
    )
    (net (code "58") (name "Net-(PCB1G-RFBK')") (class "Default")
      (node (ref "PCB1") (pin "ARFBK'") (pinfunction "RFBK'_ARFBK'") (pintype "bidirectional"))
      (node (ref "R4") (pin "2") (pinfunction "2_2") (pintype "passive"))
    )
    (net (code "59") (name "unconnected-(DD2-PA2-Pad8)") (class "Default")
      (node (ref "DD2") (pin "8") (pinfunction "PA2_8") (pintype "input"))
    )
    (net (code "60") (name "unconnected-(DD2-PA3-Pad9)") (class "Default")
      (node (ref "DD2") (pin "9") (pinfunction "PA3_9") (pintype "input"))
    )
    (net (code "61") (name "unconnected-(DD2-PA4-Pad10)") (class "Default")
      (node (ref "DD2") (pin "10") (pinfunction "PA4_10") (pintype "input"))
    )
    (net (code "62") (name "unconnected-(DD2-PA5-Pad11)") (class "Default")
      (node (ref "DD2") (pin "11") (pinfunction "PA5_11") (pintype "input"))
    )
    (net (code "63") (name "unconnected-(DD2-PA6-Pad12)") (class "Default")
      (node (ref "DD2") (pin "12") (pinfunction "PA6_12") (pintype "input"))
    )
    (net (code "64") (name "unconnected-(DD2-PA7-Pad13)") (class "Default")
      (node (ref "DD2") (pin "13") (pinfunction "PA7_13") (pintype "input"))
    )
    (net (code "65") (name "unconnected-(DD2-PA13-Pad19)") (class "Default")
      (node (ref "DD2") (pin "19") (pinfunction "PA13_19") (pintype "input"))
    )
    (net (code "66") (name "unconnected-(DD2-PB1-Pad14)") (class "Default")
      (node (ref "DD2") (pin "14") (pinfunction "PB1_14") (pintype "input"))
    )
    (net (code "67") (name "unconnected-(DD3-DREQ-Pad8)") (class "Default")
      (node (ref "DD3") (pin "8") (pinfunction "DREQ_8") (pintype "input"))
    )
    (net (code "68") (name "unconnected-(DD3-LINE2-Pad48)") (class "Default")
      (node (ref "DD3") (pin "48") (pinfunction "LINE2_48") (pintype "input"))
    )
    (net (code "69") (name "unconnected-(DD3-MICN-Pad2)") (class "Default")
      (node (ref "DD3") (pin "2") (pinfunction "MICN_2") (pintype "input"))
    )
    (net (code "70") (name "unconnected-(DD3-MICP{slash}LINE1-Pad1)") (class "Default")
      (node (ref "DD3") (pin "1") (pinfunction "MICP/LINE1_1") (pintype "input"))
    )
    (net (code "71") (name "unconnected-(DD3-SCLK-Pad28)") (class "Default")
      (node (ref "DD3") (pin "28") (pinfunction "SCLK_28") (pintype "input"))
    )
    (net (code "72") (name "unconnected-(DD3-SI-Pad29)") (class "Default")
      (node (ref "DD3") (pin "29") (pinfunction "SI_29") (pintype "input"))
    )
    (net (code "73") (name "unconnected-(DD3-SO-Pad30)") (class "Default")
      (node (ref "DD3") (pin "30") (pinfunction "SO_30") (pintype "input"))
    )
    (net (code "74") (name "unconnected-(DD3-TX-Pad27)") (class "Default")
      (node (ref "DD3") (pin "27") (pinfunction "TX_27") (pintype "input"))
    )
    (net (code "75") (name "unconnected-(DD3-VCO-Pad15)") (class "Default")
      (node (ref "DD3") (pin "15") (pinfunction "VCO_15") (pintype "input"))
    )
    (net (code "76") (name "unconnected-(DD3-~{XCS}-Pad23)") (class "Default")
      (node (ref "DD3") (pin "23") (pinfunction "~{XCS}_23") (pintype "input"))
    )
    (net (code "77") (name "unconnected-(DD3-~{XDCS{slash}BSYNC}-Pad13)") (class "Default")
      (node (ref "DD3") (pin "13") (pinfunction "~{XDCS/BSYNC}_13") (pintype "input"))
    )
    (net (code "78") (name "unconnected-(XS1-VCC-Pad1)") (class "Default")
      (node (ref "XS1") (pin "1") (pinfunction "VCC_1") (pintype "passive"))
    )
  )
)
